# driver_220v.net
KiCad netlist of a schematic drawn in EAGLE
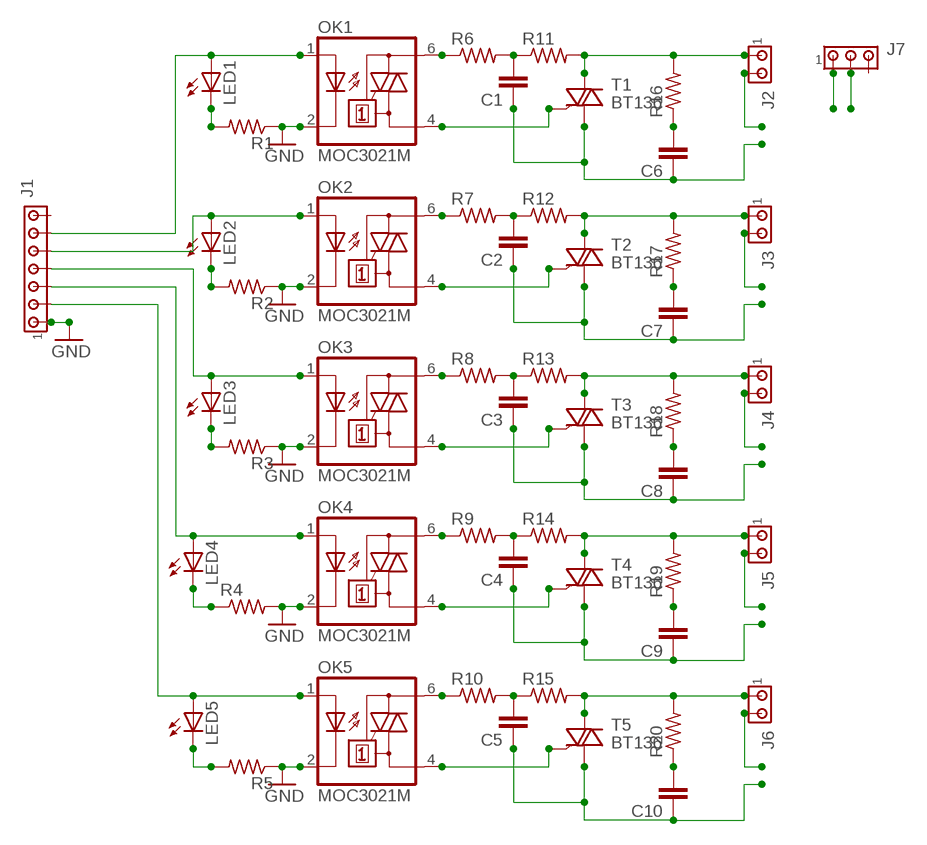
[diagram p0: schematic, sheet 1]

(export (version "E")
  (design (tool "Eeschema 10.0.6"))
  (components
    (comp (ref "C1")
      (value "C2,5-3")
      (footprint "eagle-import:C2.5-3")
      (libsource (lib "eagle-import") (part "C2,5-3"))
    )
    (comp (ref "C2")
      (value "C2,5-3")
      (footprint "eagle-import:C2.5-3")
      (libsource (lib "eagle-import") (part "C2,5-3"))
    )
    (comp (ref "C3")
      (value "C2,5-3")
      (footprint "eagle-import:C2.5-3")
      (libsource (lib "eagle-import") (part "C2,5-3"))
    )
    (comp (ref "C4")
      (value "C2,5-3")
      (footprint "eagle-import:C2.5-3")
      (libsource (lib "eagle-import") (part "C2,5-3"))
    )
    (comp (ref "C5")
      (value "C2,5-3")
      (footprint "eagle-import:C2.5-3")
      (libsource (lib "eagle-import") (part "C2,5-3"))
    )
    (comp (ref "C6")
      (value "C2,5-3")
      (footprint "eagle-import:C2.5-3")
      (libsource (lib "eagle-import") (part "C2,5-3"))
    )
    (comp (ref "C7")
      (value "C2,5-3")
      (footprint "eagle-import:C2.5-3")
      (libsource (lib "eagle-import") (part "C2,5-3"))
    )
    (comp (ref "C8")
      (value "C2,5-3")
      (footprint "eagle-import:C2.5-3")
      (libsource (lib "eagle-import") (part "C2,5-3"))
    )
    (comp (ref "C9")
      (value "C2,5-3")
      (footprint "eagle-import:C2.5-3")
      (libsource (lib "eagle-import") (part "C2,5-3"))
    )
    (comp (ref "C10")
      (value "C2,5-3")
      (footprint "eagle-import:C2.5-3")
      (libsource (lib "eagle-import") (part "C2,5-3"))
    )
    (comp (ref "J1")
      (value "MTA07-100")
      (footprint "eagle-import:10X07MTA")
      (libsource (lib "eagle-import") (part "MTA07-100"))
    )
    (comp (ref "J2")
      (value "MTA02-156")
      (footprint "eagle-import:1X2MTA")
      (libsource (lib "eagle-import") (part "MTA02-156"))
    )
    (comp (ref "J3")
      (value "MTA02-156")
      (footprint "eagle-import:1X2MTA")
      (libsource (lib "eagle-import") (part "MTA02-156"))
    )
    (comp (ref "J4")
      (value "MTA02-156")
      (footprint "eagle-import:1X2MTA")
      (libsource (lib "eagle-import") (part "MTA02-156"))
    )
    (comp (ref "J5")
      (value "MTA02-156")
      (footprint "eagle-import:1X2MTA")
      (libsource (lib "eagle-import") (part "MTA02-156"))
    )
    (comp (ref "J6")
      (value "MTA02-156")
      (footprint "eagle-import:1X2MTA")
      (libsource (lib "eagle-import") (part "MTA02-156"))
    )
    (comp (ref "J7")
      (value "MTA03-156")
      (footprint "eagle-import:1X3MTA")
      (libsource (lib "eagle-import") (part "MTA03-156"))
    )
    (comp (ref "LED1")
      (value "LED5MM")
      (footprint "eagle-import:LED5MM")
      (libsource (lib "eagle-import") (part "LED5MM"))
    )
    (comp (ref "LED2")
      (value "LED5MM")
      (footprint "eagle-import:LED5MM")
      (libsource (lib "eagle-import") (part "LED5MM"))
    )
    (comp (ref "LED3")
      (value "LED5MM")
      (footprint "eagle-import:LED5MM")
      (libsource (lib "eagle-import") (part "LED5MM"))
    )
    (comp (ref "LED4")
      (value "LED5MM")
      (footprint "eagle-import:LED5MM")
      (libsource (lib "eagle-import") (part "LED5MM"))
    )
    (comp (ref "LED5")
      (value "LED5MM")
      (footprint "eagle-import:LED5MM")
      (libsource (lib "eagle-import") (part "LED5MM"))
    )
    (comp (ref "OK1")
      (value "MOC3021M")
      (footprint "eagle-import:DIL06")
      (fields (field (name "MF") "FAIRCHILD SEMICONDUCTOR") (field (name "MPN") "MOC3021-M"))
      (libsource (lib "eagle-import") (part "MOC30M21"))
    )
    (comp (ref "OK2")
      (value "MOC3021M")
      (footprint "eagle-import:DIL06")
      (fields (field (name "MF") "FAIRCHILD SEMICONDUCTOR") (field (name "MPN") "MOC3021-M"))
      (libsource (lib "eagle-import") (part "MOC30M21"))
    )
    (comp (ref "OK3")
      (value "MOC3021M")
      (footprint "eagle-import:DIL06")
      (fields (field (name "MF") "FAIRCHILD SEMICONDUCTOR") (field (name "MPN") "MOC3021-M"))
      (libsource (lib "eagle-import") (part "MOC30M21"))
    )
    (comp (ref "OK4")
      (value "MOC3021M")
      (footprint "eagle-import:DIL06")
      (fields (field (name "MF") "FAIRCHILD SEMICONDUCTOR") (field (name "MPN") "MOC3021-M"))
      (libsource (lib "eagle-import") (part "MOC30M21"))
    )
    (comp (ref "OK5")
      (value "MOC3021M")
      (footprint "eagle-import:DIL06")
      (fields (field (name "MF") "FAIRCHILD SEMICONDUCTOR") (field (name "MPN") "MOC3021-M"))
      (libsource (lib "eagle-import") (part "MOC30M21"))
    )
    (comp (ref "R1")
      (value "R-US_R0603")
      (footprint "eagle-import:R0603")
      (libsource (lib "eagle-import") (part "resistor_R-US_R0603"))
    )
    (comp (ref "R2")
      (value "R-US_R0603")
      (footprint "eagle-import:R0603")
      (libsource (lib "eagle-import") (part "resistor_R-US_R0603"))
    )
    (comp (ref "R3")
      (value "R-US_R0603")
      (footprint "eagle-import:R0603")
      (libsource (lib "eagle-import") (part "resistor_R-US_R0603"))
    )
    (comp (ref "R4")
      (value "R-US_R0603")
      (footprint "eagle-import:R0603")
      (libsource (lib "eagle-import") (part "resistor_R-US_R0603"))
    )
    (comp (ref "R5")
      (value "R-US_R0603")
      (footprint "eagle-import:R0603")
      (libsource (lib "eagle-import") (part "resistor_R-US_R0603"))
    )
    (comp (ref "R6")
      (value "R-US_0207/10")
      (footprint "eagle-import:0207_10")
      (libsource (lib "eagle-import") (part "R-US_0207/10"))
    )
    (comp (ref "R7")
      (value "R-US_0207/10")
      (footprint "eagle-import:0207_10")
      (libsource (lib "eagle-import") (part "R-US_0207/10"))
    )
    (comp (ref "R8")
      (value "R-US_0207/10")
      (footprint "eagle-import:0207_10")
      (libsource (lib "eagle-import") (part "R-US_0207/10"))
    )
    (comp (ref "R9")
      (value "R-US_0207/10")
      (footprint "eagle-import:0207_10")
      (libsource (lib "eagle-import") (part "R-US_0207/10"))
    )
    (comp (ref "R10")
      (value "R-US_0207/10")
      (footprint "eagle-import:0207_10")
      (libsource (lib "eagle-import") (part "R-US_0207/10"))
    )
    (comp (ref "R11")
      (value "R-US_0207/10")
      (footprint "eagle-import:0207_10")
      (libsource (lib "eagle-import") (part "R-US_0207/10"))
    )
    (comp (ref "R12")
      (value "R-US_0207/10")
      (footprint "eagle-import:0207_10")
      (libsource (lib "eagle-import") (part "R-US_0207/10"))
    )
    (comp (ref "R13")
      (value "R-US_0207/10")
      (footprint "eagle-import:0207_10")
      (libsource (lib "eagle-import") (part "R-US_0207/10"))
    )
    (comp (ref "R14")
      (value "R-US_0207/10")
      (footprint "eagle-import:0207_10")
      (libsource (lib "eagle-import") (part "R-US_0207/10"))
    )
    (comp (ref "R15")
      (value "R-US_0207/10")
      (footprint "eagle-import:0207_10")
      (libsource (lib "eagle-import") (part "R-US_0207/10"))
    )
    (comp (ref "R16")
      (value "R-US_0207/10")
      (footprint "eagle-import:0207_10")
      (libsource (lib "eagle-import") (part "R-US_0207/10"))
    )
    (comp (ref "R17")
      (value "R-US_0207/10")
      (footprint "eagle-import:0207_10")
      (libsource (lib "eagle-import") (part "R-US_0207/10"))
    )
    (comp (ref "R18")
      (value "R-US_0207/10")
      (footprint "eagle-import:0207_10")
      (libsource (lib "eagle-import") (part "R-US_0207/10"))
    )
    (comp (ref "R19")
      (value "R-US_0207/10")
      (footprint "eagle-import:0207_10")
      (libsource (lib "eagle-import") (part "R-US_0207/10"))
    )
    (comp (ref "R20")
      (value "R-US_0207/10")
      (footprint "eagle-import:0207_10")
      (libsource (lib "eagle-import") (part "R-US_0207/10"))
    )
    (comp (ref "T1")
      (value "BT136")
      (footprint "eagle-import:TO220AB")
      (libsource (lib "eagle-import") (part "BT136"))
    )
    (comp (ref "T2")
      (value "BT136")
      (footprint "eagle-import:TO220AB")
      (libsource (lib "eagle-import") (part "BT136"))
    )
    (comp (ref "T3")
      (value "BT136")
      (footprint "eagle-import:TO220AB")
      (libsource (lib "eagle-import") (part "BT136"))
    )
    (comp (ref "T4")
      (value "BT136")
      (footprint "eagle-import:TO220AB")
      (libsource (lib "eagle-import") (part "BT136"))
    )
    (comp (ref "T5")
      (value "BT136")
      (footprint "eagle-import:TO220AB")
      (libsource (lib "eagle-import") (part "BT136"))
    )
  )
  (nets
    (net (code "1") (name "/LIVE") (class "Default")
      (node (ref "J2") (pin "2") (pinfunction "2_2") (pintype "passive"))
      (node (ref "J3") (pin "2") (pinfunction "2_2") (pintype "passive"))
      (node (ref "J4") (pin "2") (pinfunction "2_2") (pintype "passive"))
      (node (ref "J5") (pin "2") (pinfunction "2_2") (pintype "passive"))
      (node (ref "J6") (pin "2") (pinfunction "2_2") (pintype "passive"))
      (node (ref "J7") (pin "1") (pinfunction "1_1") (pintype "passive"))
    )
    (net (code "2") (name "/NEUTRAL") (class "Default")
      (node (ref "C1") (pin "1") (pinfunction "1_1") (pintype "passive"))
      (node (ref "C10") (pin "1") (pinfunction "1_1") (pintype "passive"))
      (node (ref "C2") (pin "1") (pinfunction "1_1") (pintype "passive"))
      (node (ref "C3") (pin "1") (pinfunction "1_1") (pintype "passive"))
      (node (ref "C4") (pin "1") (pinfunction "1_1") (pintype "passive"))
      (node (ref "C5") (pin "1") (pinfunction "1_1") (pintype "passive"))
      (node (ref "C6") (pin "1") (pinfunction "1_1") (pintype "passive"))
      (node (ref "C7") (pin "1") (pinfunction "1_1") (pintype "passive"))
      (node (ref "C8") (pin "1") (pinfunction "1_1") (pintype "passive"))
      (node (ref "C9") (pin "1") (pinfunction "1_1") (pintype "passive"))
      (node (ref "J7") (pin "2") (pinfunction "2_2") (pintype "passive"))
      (node (ref "T1") (pin "1") (pinfunction "A1_1") (pintype "passive"))
      (node (ref "T2") (pin "1") (pinfunction "A1_1") (pintype "passive"))
      (node (ref "T3") (pin "1") (pinfunction "A1_1") (pintype "passive"))
      (node (ref "T4") (pin "1") (pinfunction "A1_1") (pintype "passive"))
      (node (ref "T5") (pin "1") (pinfunction "A1_1") (pintype "passive"))
    )
    (net (code "3") (name "GND") (class "Default")
      (node (ref "J1") (pin "1") (pinfunction "1_1") (pintype "passive"))
      (node (ref "OK1") (pin "2") (pinfunction "C_2") (pintype "passive"))
      (node (ref "OK2") (pin "2") (pinfunction "C_2") (pintype "passive"))
      (node (ref "OK3") (pin "2") (pinfunction "C_2") (pintype "passive"))
      (node (ref "OK4") (pin "2") (pinfunction "C_2") (pintype "passive"))
      (node (ref "OK5") (pin "2") (pinfunction "C_2") (pintype "passive"))
      (node (ref "R1") (pin "1") (pinfunction "1_1") (pintype "passive"))
      (node (ref "R2") (pin "1") (pinfunction "1_1") (pintype "passive"))
      (node (ref "R3") (pin "1") (pinfunction "1_1") (pintype "passive"))
      (node (ref "R4") (pin "2") (pinfunction "2_2") (pintype "passive"))
      (node (ref "R5") (pin "1") (pinfunction "1_1") (pintype "passive"))
    )
    (net (code "4") (name "Net-(C1-Pad2)") (class "Default")
      (node (ref "C1") (pin "2") (pinfunction "2_2") (pintype "passive"))
      (node (ref "R11") (pin "1") (pinfunction "1_1") (pintype "passive"))
      (node (ref "R6") (pin "2") (pinfunction "2_2") (pintype "passive"))
    )
    (net (code "5") (name "Net-(C2-Pad2)") (class "Default")
      (node (ref "C2") (pin "2") (pinfunction "2_2") (pintype "passive"))
      (node (ref "R12") (pin "1") (pinfunction "1_1") (pintype "passive"))
      (node (ref "R7") (pin "2") (pinfunction "2_2") (pintype "passive"))
    )
    (net (code "6") (name "Net-(C3-Pad2)") (class "Default")
      (node (ref "C3") (pin "2") (pinfunction "2_2") (pintype "passive"))
      (node (ref "R13") (pin "1") (pinfunction "1_1") (pintype "passive"))
      (node (ref "R8") (pin "2") (pinfunction "2_2") (pintype "passive"))
    )
    (net (code "7") (name "Net-(C4-Pad2)") (class "Default")
      (node (ref "C4") (pin "2") (pinfunction "2_2") (pintype "passive"))
      (node (ref "R14") (pin "1") (pinfunction "1_1") (pintype "passive"))
      (node (ref "R9") (pin "2") (pinfunction "2_2") (pintype "passive"))
    )
    (net (code "8") (name "Net-(C5-Pad2)") (class "Default")
      (node (ref "C5") (pin "2") (pinfunction "2_2") (pintype "passive"))
      (node (ref "R10") (pin "2") (pinfunction "2_2") (pintype "passive"))
      (node (ref "R15") (pin "1") (pinfunction "1_1") (pintype "passive"))
    )
    (net (code "9") (name "Net-(C6-Pad2)") (class "Default")
      (node (ref "C6") (pin "2") (pinfunction "2_2") (pintype "passive"))
      (node (ref "R16") (pin "1") (pinfunction "1_1") (pintype "passive"))
    )
    (net (code "10") (name "Net-(C7-Pad2)") (class "Default")
      (node (ref "C7") (pin "2") (pinfunction "2_2") (pintype "passive"))
      (node (ref "R17") (pin "1") (pinfunction "1_1") (pintype "passive"))
    )
    (net (code "11") (name "Net-(C8-Pad2)") (class "Default")
      (node (ref "C8") (pin "2") (pinfunction "2_2") (pintype "passive"))
      (node (ref "R18") (pin "1") (pinfunction "1_1") (pintype "passive"))
    )
    (net (code "12") (name "Net-(C9-Pad2)") (class "Default")
      (node (ref "C9") (pin "2") (pinfunction "2_2") (pintype "passive"))
      (node (ref "R19") (pin "1") (pinfunction "1_1") (pintype "passive"))
    )
    (net (code "13") (name "Net-(C10-Pad2)") (class "Default")
      (node (ref "C10") (pin "2") (pinfunction "2_2") (pintype "passive"))
      (node (ref "R20") (pin "1") (pinfunction "1_1") (pintype "passive"))
    )
    (net (code "14") (name "Net-(LED1-C)") (class "Default")
      (node (ref "LED1") (pin "K") (pinfunction "C_K") (pintype "passive"))
      (node (ref "R1") (pin "2") (pinfunction "2_2") (pintype "passive"))
    )
    (net (code "15") (name "Net-(LED2-C)") (class "Default")
      (node (ref "LED2") (pin "K") (pinfunction "C_K") (pintype "passive"))
      (node (ref "R2") (pin "2") (pinfunction "2_2") (pintype "passive"))
    )
    (net (code "16") (name "Net-(LED3-C)") (class "Default")
      (node (ref "LED3") (pin "K") (pinfunction "C_K") (pintype "passive"))
      (node (ref "R3") (pin "2") (pinfunction "2_2") (pintype "passive"))
    )
    (net (code "17") (name "Net-(LED4-C)") (class "Default")
      (node (ref "LED4") (pin "K") (pinfunction "C_K") (pintype "passive"))
      (node (ref "R4") (pin "1") (pinfunction "1_1") (pintype "passive"))
    )
    (net (code "18") (name "Net-(LED5-C)") (class "Default")
      (node (ref "LED5") (pin "K") (pinfunction "C_K") (pintype "passive"))
      (node (ref "R5") (pin "2") (pinfunction "2_2") (pintype "passive"))
    )
    (net (code "19") (name "Net-(OK1-A)") (class "Default")
      (node (ref "J1") (pin "6") (pinfunction "6_6") (pintype "passive"))
      (node (ref "LED1") (pin "A") (pinfunction "A_A") (pintype "passive"))
      (node (ref "OK1") (pin "1") (pinfunction "A_1") (pintype "passive"))
    )
    (net (code "20") (name "Net-(OK1-A1)") (class "Default")
      (node (ref "OK1") (pin "4") (pinfunction "A1_4") (pintype "passive"))
      (node (ref "T1") (pin "3") (pinfunction "G_3") (pintype "passive"))
    )
    (net (code "21") (name "Net-(OK1-A2)") (class "Default")
      (node (ref "OK1") (pin "6") (pinfunction "A2_6") (pintype "passive"))
      (node (ref "R6") (pin "1") (pinfunction "1_1") (pintype "passive"))
    )
    (net (code "22") (name "Net-(OK2-A)") (class "Default")
      (node (ref "J1") (pin "5") (pinfunction "5_5") (pintype "passive"))
      (node (ref "LED2") (pin "A") (pinfunction "A_A") (pintype "passive"))
      (node (ref "OK2") (pin "1") (pinfunction "A_1") (pintype "passive"))
    )
    (net (code "23") (name "Net-(OK2-A1)") (class "Default")
      (node (ref "OK2") (pin "4") (pinfunction "A1_4") (pintype "passive"))
      (node (ref "T2") (pin "3") (pinfunction "G_3") (pintype "passive"))
    )
    (net (code "24") (name "Net-(OK2-A2)") (class "Default")
      (node (ref "OK2") (pin "6") (pinfunction "A2_6") (pintype "passive"))
      (node (ref "R7") (pin "1") (pinfunction "1_1") (pintype "passive"))
    )
    (net (code "25") (name "Net-(OK3-A)") (class "Default")
      (node (ref "J1") (pin "4") (pinfunction "4_4") (pintype "passive"))
      (node (ref "LED3") (pin "A") (pinfunction "A_A") (pintype "passive"))
      (node (ref "OK3") (pin "1") (pinfunction "A_1") (pintype "passive"))
    )
    (net (code "26") (name "Net-(OK3-A1)") (class "Default")
      (node (ref "OK3") (pin "4") (pinfunction "A1_4") (pintype "passive"))
      (node (ref "T3") (pin "3") (pinfunction "G_3") (pintype "passive"))
    )
    (net (code "27") (name "Net-(OK3-A2)") (class "Default")
      (node (ref "OK3") (pin "6") (pinfunction "A2_6") (pintype "passive"))
      (node (ref "R8") (pin "1") (pinfunction "1_1") (pintype "passive"))
    )
    (net (code "28") (name "Net-(OK4-A)") (class "Default")
      (node (ref "J1") (pin "3") (pinfunction "3_3") (pintype "passive"))
      (node (ref "LED4") (pin "A") (pinfunction "A_A") (pintype "passive"))
      (node (ref "OK4") (pin "1") (pinfunction "A_1") (pintype "passive"))
    )
    (net (code "29") (name "Net-(OK4-A1)") (class "Default")
      (node (ref "OK4") (pin "4") (pinfunction "A1_4") (pintype "passive"))
      (node (ref "T4") (pin "3") (pinfunction "G_3") (pintype "passive"))
    )
    (net (code "30") (name "Net-(OK4-A2)") (class "Default")
      (node (ref "OK4") (pin "6") (pinfunction "A2_6") (pintype "passive"))
      (node (ref "R9") (pin "1") (pinfunction "1_1") (pintype "passive"))
    )
    (net (code "31") (name "Net-(OK5-A)") (class "Default")
      (node (ref "J1") (pin "2") (pinfunction "2_2") (pintype "passive"))
      (node (ref "LED5") (pin "A") (pinfunction "A_A") (pintype "passive"))
      (node (ref "OK5") (pin "1") (pinfunction "A_1") (pintype "passive"))
    )
    (net (code "32") (name "Net-(OK5-A1)") (class "Default")
      (node (ref "OK5") (pin "4") (pinfunction "A1_4") (pintype "passive"))
      (node (ref "T5") (pin "3") (pinfunction "G_3") (pintype "passive"))
    )
    (net (code "33") (name "Net-(OK5-A2)") (class "Default")
      (node (ref "OK5") (pin "6") (pinfunction "A2_6") (pintype "passive"))
      (node (ref "R10") (pin "1") (pinfunction "1_1") (pintype "passive"))
    )
    (net (code "34") (name "Net-(T1-A2)") (class "Default")
      (node (ref "J2") (pin "1") (pinfunction "1_1") (pintype "passive"))
      (node (ref "R11") (pin "2") (pinfunction "2_2") (pintype "passive"))
      (node (ref "R16") (pin "2") (pinfunction "2_2") (pintype "passive"))
      (node (ref "T1") (pin "2") (pinfunction "A2_2") (pintype "passive"))
    )
    (net (code "35") (name "Net-(T2-A2)") (class "Default")
      (node (ref "J3") (pin "1") (pinfunction "1_1") (pintype "passive"))
      (node (ref "R12") (pin "2") (pinfunction "2_2") (pintype "passive"))
      (node (ref "R17") (pin "2") (pinfunction "2_2") (pintype "passive"))
      (node (ref "T2") (pin "2") (pinfunction "A2_2") (pintype "passive"))
    )
    (net (code "36") (name "Net-(T3-A2)") (class "Default")
      (node (ref "J4") (pin "1") (pinfunction "1_1") (pintype "passive"))
      (node (ref "R13") (pin "2") (pinfunction "2_2") (pintype "passive"))
      (node (ref "R18") (pin "2") (pinfunction "2_2") (pintype "passive"))
      (node (ref "T3") (pin "2") (pinfunction "A2_2") (pintype "passive"))
    )
    (net (code "37") (name "Net-(T4-A2)") (class "Default")
      (node (ref "J5") (pin "1") (pinfunction "1_1") (pintype "passive"))
      (node (ref "R14") (pin "2") (pinfunction "2_2") (pintype "passive"))
      (node (ref "R19") (pin "2") (pinfunction "2_2") (pintype "passive"))
      (node (ref "T4") (pin "2") (pinfunction "A2_2") (pintype "passive"))
    )
    (net (code "38") (name "Net-(T5-A2)") (class "Default")
      (node (ref "J6") (pin "1") (pinfunction "1_1") (pintype "passive"))
      (node (ref "R15") (pin "2") (pinfunction "2_2") (pintype "passive"))
      (node (ref "R20") (pin "2") (pinfunction "2_2") (pintype "passive"))
      (node (ref "T5") (pin "2") (pinfunction "A2_2") (pintype "passive"))
    )
    (net (code "39") (name "unconnected-(J1-Pad7)") (class "Default")
      (node (ref "J1") (pin "7") (pinfunction "7_7") (pintype "passive"))
    )
    (net (code "40") (name "unconnected-(J7-Pad3)") (class "Default")
      (node (ref "J7") (pin "3") (pinfunction "3_3") (pintype "passive"))
    )
  )
)
